# datalogger_v01_1284.net
KiCad netlist of a schematic drawn in EAGLE
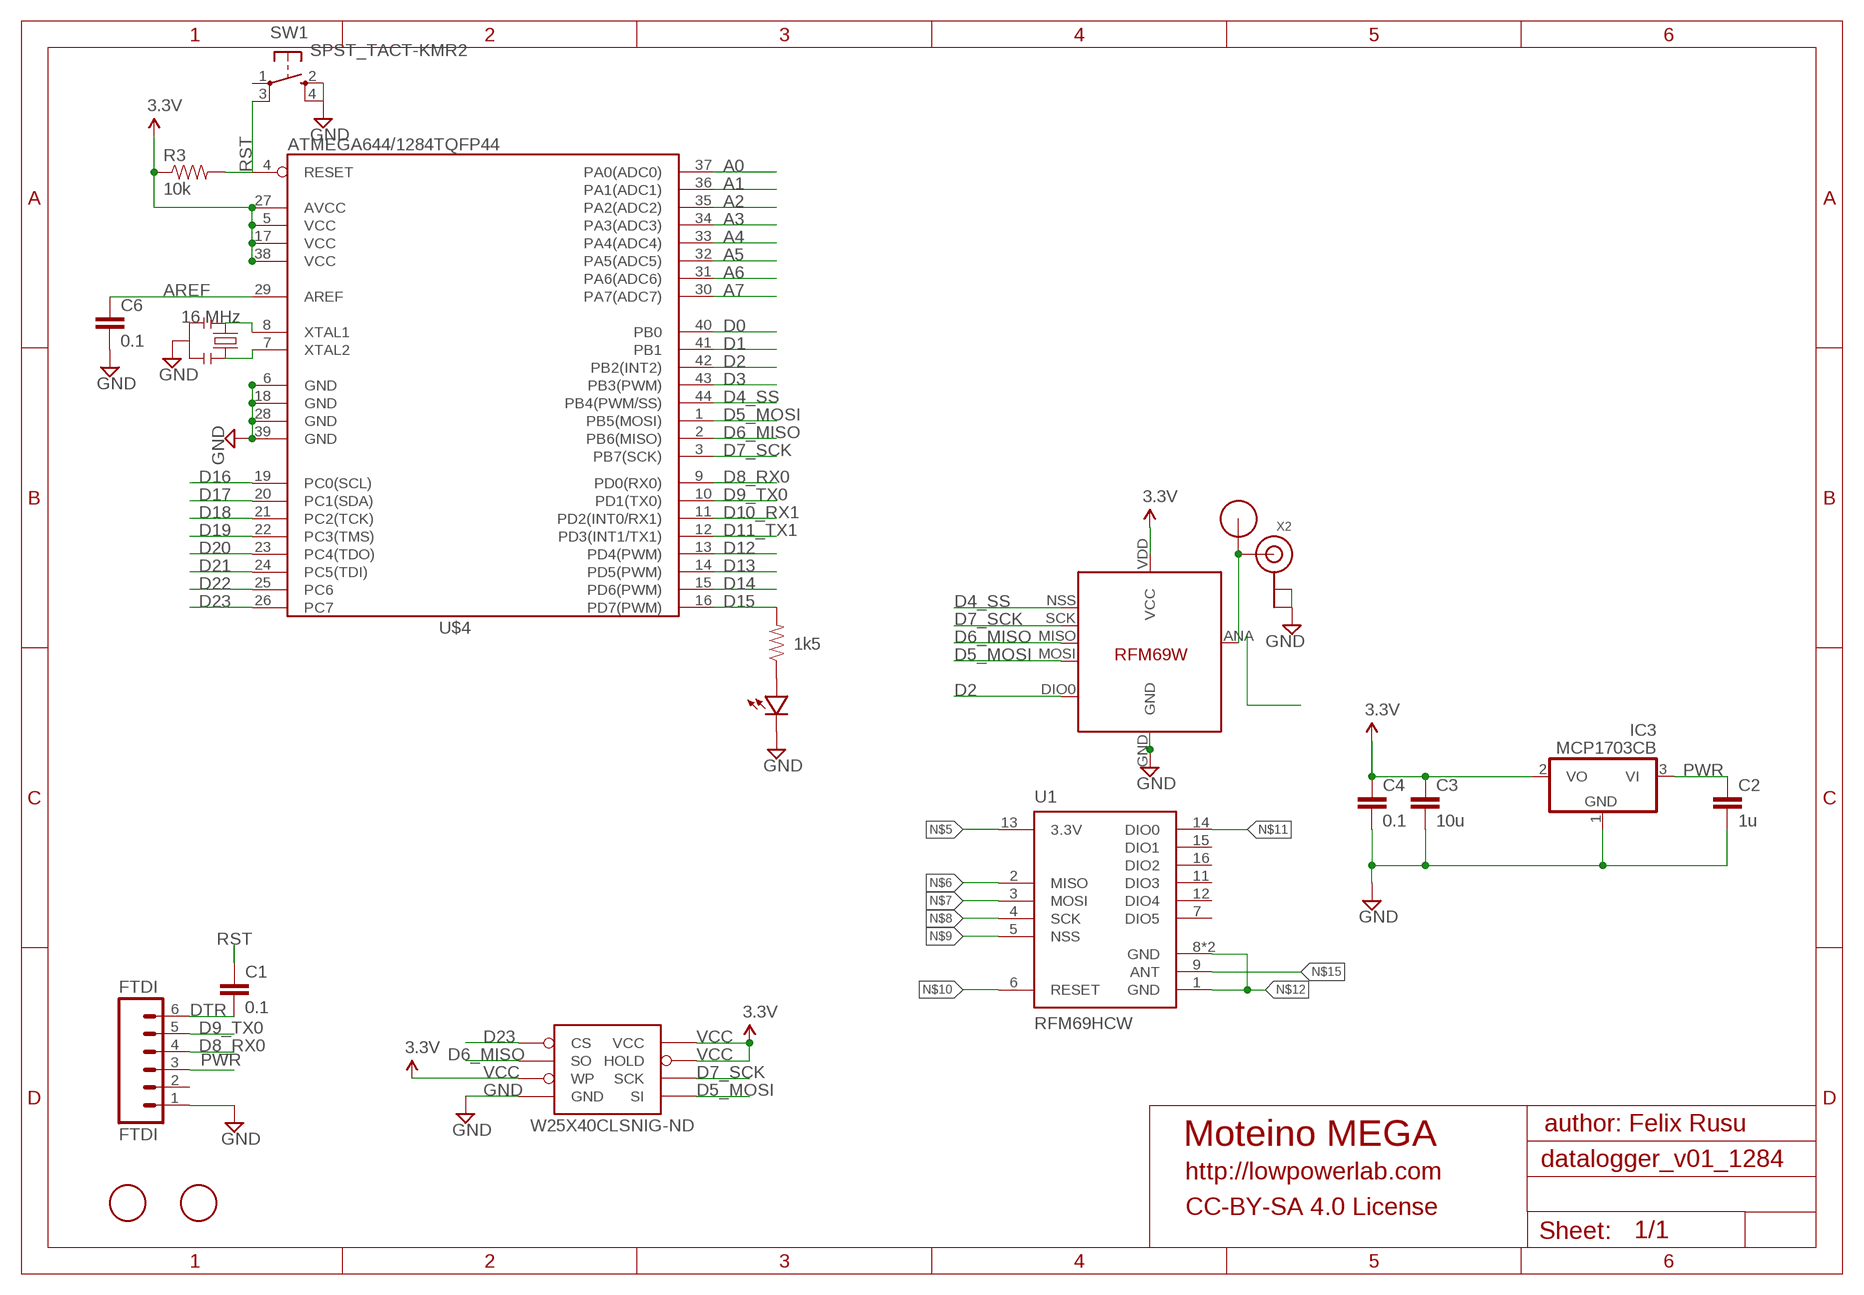
[diagram p0: schematic, sheet 1]

(export (version "E")
  (design (tool "Eeschema 10.0.6"))
  (components
    (comp (ref "C1")
      (value "0.1")
      (footprint "eagle-import:0603-CAP")
      (libsource (lib "eagle-import") (part "CAP0603-CAP"))
    )
    (comp (ref "C2")
      (value "1u")
      (footprint "eagle-import:0603-CAP")
      (libsource (lib "eagle-import") (part "CAP0603-CAP"))
    )
    (comp (ref "C3")
      (value "10u")
      (footprint "eagle-import:0805-CAP")
      (libsource (lib "eagle-import") (part "CAP0805-CAP"))
    )
    (comp (ref "C4")
      (value "0.1")
      (footprint "eagle-import:0603-CAP")
      (libsource (lib "eagle-import") (part "CAP0603-CAP"))
    )
    (comp (ref "C6")
      (value "0.1")
      (footprint "eagle-import:0603-CAP")
      (libsource (lib "eagle-import") (part "CAP0603-CAP"))
    )
    (comp (ref "FTDI")
      (value "FTDI")
      (footprint "eagle-import:1X06")
      (libsource (lib "eagle-import") (part "M06SIP"))
    )
    (comp (ref "IC3")
      (value "MCP1703CB")
      (footprint "eagle-import:SOT23")
      (libsource (lib "eagle-import") (part "MCP1703CB"))
    )
    (comp (ref "R2")
      (value "1k5")
      (footprint "eagle-import:0603-RES")
      (libsource (lib "eagle-import") (part "RESISTOR0603-RES"))
    )
    (comp (ref "R3")
      (value "10k")
      (footprint "eagle-import:0603-RES")
      (libsource (lib "eagle-import") (part "RESISTOR0603-RES"))
    )
    (comp (ref "SW1")
      (value "SPST_TACT-KMR2")
      (footprint "eagle-import:KMR2")
      (libsource (lib "eagle-import") (part "SPST_TACT-KMR2"))
    )
    (comp (ref "U$1")
      (value "RFM12B_ANTENNA")
      (footprint "eagle-import:RFM12B-ANTENNA")
      (libsource (lib "eagle-import") (part "RFM12B_ANTENNA"))
    )
    (comp (ref "U$2")
      (value "FIDUCIAL")
      (footprint "eagle-import:FIDUCIAL_1MM")
      (libsource (lib "eagle-import") (part "FIDUCIAL"))
    )
    (comp (ref "U$4")
      (value "ATMEGA644/1284TQFP44")
      (footprint "eagle-import:TQFP44")
      (libsource (lib "eagle-import") (part "ATMEGA644/1284TQFP44"))
    )
    (comp (ref "U$5")
      (value "RFM69")
      (footprint "eagle-import:RFM69W-MINPADS")
      (libsource (lib "eagle-import") (part "RFM69"))
    )
    (comp (ref "U$6")
      (value "LED0603")
      (footprint "eagle-import:0603-LED")
      (libsource (lib "eagle-import") (part "LED0603"))
    )
    (comp (ref "U$7")
      (value "FIDUCIAL")
      (footprint "eagle-import:FIDUCIAL_1MM")
      (libsource (lib "eagle-import") (part "FIDUCIAL"))
    )
    (comp (ref "U1")
      (value "RFM69HCW")
      (footprint "eagle-import:RFM69HCW-XXXS2")
      (libsource (lib "eagle-import") (part "RFM69HCW"))
    )
    (comp (ref "W25X40CLSNIG-ND")
      (value "AT25F512BWIDE_5.3MM")
      (footprint "eagle-import:SO08WIDE")
      (libsource (lib "eagle-import") (part "AT25F512BWIDE_5.3MM"))
    )
    (comp (ref "X1")
      (value "16 MHz")
      (footprint "eagle-import:RESONATOR-SMD")
      (libsource (lib "eagle-import") (part "RESONATORSMD"))
    )
    (comp (ref "X2")
      (value "ANTENNA_U.FL")
      (footprint "eagle-import:U.FL")
      (libsource (lib "eagle-import") (part "ANTENNA_U.FL"))
    )
  )
  (nets
    (net (code "1") (name "/A0") (class "Default")
      (node (ref "U$4") (pin "37") (pinfunction "PA0(ADC0)_37") (pintype "bidirectional"))
    )
    (net (code "2") (name "/A1") (class "Default")
      (node (ref "U$4") (pin "36") (pinfunction "PA1(ADC1)_36") (pintype "bidirectional"))
    )
    (net (code "3") (name "/A2") (class "Default")
      (node (ref "U$4") (pin "35") (pinfunction "PA2(ADC2)_35") (pintype "bidirectional"))
    )
    (net (code "4") (name "/A3") (class "Default")
      (node (ref "U$4") (pin "34") (pinfunction "PA3(ADC3)_34") (pintype "bidirectional"))
    )
    (net (code "5") (name "/A4") (class "Default")
      (node (ref "U$4") (pin "33") (pinfunction "PA4(ADC4)_33") (pintype "bidirectional"))
    )
    (net (code "6") (name "/A5") (class "Default")
      (node (ref "U$4") (pin "32") (pinfunction "PA5(ADC5)_32") (pintype "bidirectional"))
    )
    (net (code "7") (name "/A6") (class "Default")
      (node (ref "U$4") (pin "31") (pinfunction "PA6(ADC6)_31") (pintype "bidirectional"))
    )
    (net (code "8") (name "/A7") (class "Default")
      (node (ref "U$4") (pin "30") (pinfunction "PA7(ADC7)_30") (pintype "bidirectional"))
    )
    (net (code "9") (name "/AREF") (class "Default")
      (node (ref "C6") (pin "1") (pinfunction "1_1") (pintype "passive"))
      (node (ref "U$4") (pin "29") (pinfunction "AREF_29") (pintype "bidirectional"))
    )
    (net (code "10") (name "/D0") (class "Default")
      (node (ref "U$4") (pin "40") (pinfunction "PB0_40") (pintype "bidirectional"))
    )
    (net (code "11") (name "/D1") (class "Default")
      (node (ref "U$4") (pin "41") (pinfunction "PB1_41") (pintype "bidirectional"))
    )
    (net (code "12") (name "/D2") (class "Default")
      (node (ref "U$4") (pin "42") (pinfunction "PB2(INT2)_42") (pintype "bidirectional"))
      (node (ref "U$5") (pin "DIO0") (pinfunction "DIO0_DIO0") (pintype "open_collector"))
    )
    (net (code "13") (name "/D3") (class "Default")
      (node (ref "U$4") (pin "43") (pinfunction "PB3(PWM)_43") (pintype "bidirectional"))
    )
    (net (code "14") (name "/D4_SS") (class "Default")
      (node (ref "U$4") (pin "44") (pinfunction "PB4(PWM/SS)_44") (pintype "bidirectional"))
      (node (ref "U$5") (pin "NSS") (pinfunction "SEL_NSS") (pintype "input"))
    )
    (net (code "15") (name "/D5_MOSI") (class "Default")
      (node (ref "U$4") (pin "1") (pinfunction "PB5(MOSI)_1") (pintype "bidirectional"))
      (node (ref "U$5") (pin "MOSI") (pinfunction "MOSI_MOSI") (pintype "output"))
      (node (ref "W25X40CLSNIG-ND") (pin "5") (pinfunction "SI_5") (pintype "bidirectional"))
    )
    (net (code "16") (name "/D6_MISO") (class "Default")
      (node (ref "U$4") (pin "2") (pinfunction "PB6(MISO)_2") (pintype "bidirectional"))
      (node (ref "U$5") (pin "MISO") (pinfunction "MISO_MISO") (pintype "input"))
      (node (ref "W25X40CLSNIG-ND") (pin "2") (pinfunction "SO_2") (pintype "bidirectional"))
    )
    (net (code "17") (name "/D7_SCK") (class "Default")
      (node (ref "U$4") (pin "3") (pinfunction "PB7(SCK)_3") (pintype "bidirectional"))
      (node (ref "U$5") (pin "SCK") (pinfunction "SCK_SCK") (pintype "input"))
      (node (ref "W25X40CLSNIG-ND") (pin "6") (pinfunction "SCK_6") (pintype "bidirectional"))
    )
    (net (code "18") (name "/D8_RX0") (class "Default")
      (node (ref "FTDI") (pin "4") (pinfunction "4_4") (pintype "passive"))
      (node (ref "U$4") (pin "9") (pinfunction "PD0(RX0)_9") (pintype "bidirectional"))
    )
    (net (code "19") (name "/D9_TX0") (class "Default")
      (node (ref "FTDI") (pin "5") (pinfunction "5_5") (pintype "passive"))
      (node (ref "U$4") (pin "10") (pinfunction "PD1(TX0)_10") (pintype "bidirectional"))
    )
    (net (code "20") (name "/D10_RX1") (class "Default")
      (node (ref "U$4") (pin "11") (pinfunction "PD2(INT0/RX1)_11") (pintype "bidirectional"))
    )
    (net (code "21") (name "/D11_TX1") (class "Default")
      (node (ref "U$4") (pin "12") (pinfunction "PD3(INT1/TX1)_12") (pintype "bidirectional"))
    )
    (net (code "22") (name "/D12") (class "Default")
      (node (ref "U$4") (pin "13") (pinfunction "PD4(PWM)_13") (pintype "bidirectional"))
    )
    (net (code "23") (name "/D13") (class "Default")
      (node (ref "U$4") (pin "14") (pinfunction "PD5(PWM)_14") (pintype "bidirectional"))
    )
    (net (code "24") (name "/D14") (class "Default")
      (node (ref "U$4") (pin "15") (pinfunction "PD6(PWM)_15") (pintype "bidirectional"))
    )
    (net (code "25") (name "/D15") (class "Default")
      (node (ref "R2") (pin "2") (pinfunction "2_2") (pintype "passive"))
      (node (ref "U$4") (pin "16") (pinfunction "PD7(PWM)_16") (pintype "bidirectional"))
    )
    (net (code "26") (name "/D16") (class "Default")
      (node (ref "U$4") (pin "19") (pinfunction "PC0(SCL)_19") (pintype "bidirectional"))
    )
    (net (code "27") (name "/D17") (class "Default")
      (node (ref "U$4") (pin "20") (pinfunction "PC1(SDA)_20") (pintype "bidirectional"))
    )
    (net (code "28") (name "/D18") (class "Default")
      (node (ref "U$4") (pin "21") (pinfunction "PC2(TCK)_21") (pintype "bidirectional"))
    )
    (net (code "29") (name "/D19") (class "Default")
      (node (ref "U$4") (pin "22") (pinfunction "PC3(TMS)_22") (pintype "bidirectional"))
    )
    (net (code "30") (name "/D20") (class "Default")
      (node (ref "U$4") (pin "23") (pinfunction "PC4(TDO)_23") (pintype "bidirectional"))
    )
    (net (code "31") (name "/D21") (class "Default")
      (node (ref "U$4") (pin "24") (pinfunction "PC5(TDI)_24") (pintype "bidirectional"))
    )
    (net (code "32") (name "/D22") (class "Default")
      (node (ref "U$4") (pin "25") (pinfunction "PC6_25") (pintype "bidirectional"))
    )
    (net (code "33") (name "/D23") (class "Default")
      (node (ref "U$4") (pin "26") (pinfunction "PC7_26") (pintype "bidirectional"))
      (node (ref "W25X40CLSNIG-ND") (pin "1") (pinfunction "CS_1") (pintype "bidirectional"))
    )
    (net (code "34") (name "/DTR") (class "Default")
      (node (ref "C1") (pin "2") (pinfunction "2_2") (pintype "passive"))
      (node (ref "FTDI") (pin "6") (pinfunction "6_6") (pintype "passive"))
    )
    (net (code "35") (name "/PWR") (class "Default")
      (node (ref "C2") (pin "1") (pinfunction "1_1") (pintype "passive"))
      (node (ref "FTDI") (pin "3") (pinfunction "3_3") (pintype "passive"))
      (node (ref "IC3") (pin "3") (pinfunction "VI_3") (pintype "input"))
    )
    (net (code "36") (name "/RST") (class "Default")
      (node (ref "C1") (pin "1") (pinfunction "1_1") (pintype "passive"))
      (node (ref "R3") (pin "2") (pinfunction "2_2") (pintype "passive"))
      (node (ref "SW1") (pin "3") (pinfunction "P1_3") (pintype "passive"))
      (node (ref "U$4") (pin "4") (pinfunction "RESET_4") (pintype "bidirectional"))
    )
    (net (code "37") (name "3.3V") (class "Default")
      (node (ref "C3") (pin "1") (pinfunction "1_1") (pintype "passive"))
      (node (ref "C4") (pin "1") (pinfunction "1_1") (pintype "passive"))
      (node (ref "IC3") (pin "2") (pinfunction "VO_2") (pintype "passive"))
      (node (ref "R3") (pin "1") (pinfunction "1_1") (pintype "passive"))
      (node (ref "U$4") (pin "17") (pinfunction "VCC_17") (pintype "bidirectional"))
      (node (ref "U$4") (pin "27") (pinfunction "AVCC_27") (pintype "bidirectional"))
      (node (ref "U$4") (pin "38") (pinfunction "VCC_38") (pintype "bidirectional"))
      (node (ref "U$4") (pin "5") (pinfunction "VCC_5") (pintype "bidirectional"))
      (node (ref "U$5") (pin "VDD") (pinfunction "VCC_VDD") (pintype "power_in"))
      (node (ref "W25X40CLSNIG-ND") (pin "3") (pinfunction "WP_3") (pintype "bidirectional"))
      (node (ref "W25X40CLSNIG-ND") (pin "7") (pinfunction "HOLD_7") (pintype "bidirectional"))
      (node (ref "W25X40CLSNIG-ND") (pin "8") (pinfunction "VCC_8") (pintype "bidirectional"))
    )
    (net (code "38") (name "GND") (class "Default")
      (node (ref "C2") (pin "2") (pinfunction "2_2") (pintype "passive"))
      (node (ref "C3") (pin "2") (pinfunction "2_2") (pintype "passive"))
      (node (ref "C4") (pin "2") (pinfunction "2_2") (pintype "passive"))
      (node (ref "C6") (pin "2") (pinfunction "2_2") (pintype "passive"))
      (node (ref "FTDI") (pin "1") (pinfunction "1_1") (pintype "passive"))
      (node (ref "IC3") (pin "1") (pinfunction "GND_1") (pintype "passive"))
      (node (ref "SW1") (pin "2") (pinfunction "S_2") (pintype "passive"))
      (node (ref "SW1") (pin "4") (pinfunction "S1_4") (pintype "passive"))
      (node (ref "U$4") (pin "18") (pinfunction "GND_18") (pintype "bidirectional"))
      (node (ref "U$4") (pin "28") (pinfunction "GND_28") (pintype "bidirectional"))
      (node (ref "U$4") (pin "39") (pinfunction "GND_39") (pintype "bidirectional"))
      (node (ref "U$4") (pin "6") (pinfunction "GND_6") (pintype "bidirectional"))
      (node (ref "U$5") (pin "GND") (pinfunction "GND_GND") (pintype "power_in"))
      (node (ref "U$6") (pin "MINUS") (pinfunction "MINUS_MINUS") (pintype "passive"))
      (node (ref "W25X40CLSNIG-ND") (pin "4") (pinfunction "GND_4") (pintype "bidirectional"))
      (node (ref "X1") (pin "2") (pinfunction "2_2") (pintype "passive"))
      (node (ref "X2") (pin "1") (pinfunction "GND_1") (pintype "passive"))
      (node (ref "X2") (pin "2") (pinfunction "GND_2") (pintype "passive"))
    )
    (net (code "39") (name "N$5") (class "Default")
      (node (ref "U1") (pin "13") (pinfunction "3.3V_13") (pintype "power_in"))
    )
    (net (code "40") (name "N$6") (class "Default")
      (node (ref "U1") (pin "2") (pinfunction "MISO_2") (pintype "bidirectional"))
    )
    (net (code "41") (name "N$7") (class "Default")
      (node (ref "U1") (pin "3") (pinfunction "MOSI_3") (pintype "input"))
    )
    (net (code "42") (name "N$8") (class "Default")
      (node (ref "U1") (pin "4") (pinfunction "SCK_4") (pintype "input"))
    )
    (net (code "43") (name "N$9") (class "Default")
      (node (ref "U1") (pin "5") (pinfunction "NSS_5") (pintype "input"))
    )
    (net (code "44") (name "N$10") (class "Default")
      (node (ref "U1") (pin "6") (pinfunction "RESET_6") (pintype "input"))
    )
    (net (code "45") (name "N$11") (class "Default")
      (node (ref "U1") (pin "14") (pinfunction "DIO0_14") (pintype "bidirectional"))
    )
    (net (code "46") (name "N$12") (class "Default")
      (node (ref "U1") (pin "1") (pinfunction "GND_1") (pintype "power_in"))
      (node (ref "U1") (pin "10") (pinfunction "GND_10") (pintype "power_in"))
      (node (ref "U1") (pin "8") (pinfunction "GND_8") (pintype "power_in"))
    )
    (net (code "47") (name "N$15") (class "Default")
      (node (ref "U1") (pin "9") (pinfunction "ANT_9") (pintype "passive"))
    )
    (net (code "48") (name "Net-(R2-Pad1)") (class "Default")
      (node (ref "R2") (pin "1") (pinfunction "1_1") (pintype "passive"))
      (node (ref "U$6") (pin "PLUS") (pinfunction "PLUS_PLUS") (pintype "passive"))
    )
    (net (code "49") (name "Net-(U$1-1)") (class "Default")
      (node (ref "U$1") (pin "P$1") (pinfunction "1_P$1") (pintype "bidirectional"))
      (node (ref "U$5") (pin "ANA") (pinfunction "ANT_ANA") (pintype "passive"))
      (node (ref "X2") (pin "3") (pinfunction "SIGNAL_3") (pintype "passive"))
    )
    (net (code "50") (name "Net-(U$4-XTAL1)") (class "Default")
      (node (ref "U$4") (pin "8") (pinfunction "XTAL1_8") (pintype "bidirectional"))
      (node (ref "X1") (pin "1") (pinfunction "1_1") (pintype "passive"))
    )
    (net (code "51") (name "Net-(U$4-XTAL2)") (class "Default")
      (node (ref "U$4") (pin "7") (pinfunction "XTAL2_7") (pintype "bidirectional"))
      (node (ref "X1") (pin "3") (pinfunction "3_3") (pintype "passive"))
    )
    (net (code "52") (name "unconnected-(FTDI-Pad2)") (class "Default")
      (node (ref "FTDI") (pin "2") (pinfunction "2_2") (pintype "passive"))
    )
    (net (code "53") (name "unconnected-(SW1-P-Pad1)") (class "Default")
      (node (ref "SW1") (pin "1") (pinfunction "P_1") (pintype "passive"))
    )
    (net (code "54") (name "unconnected-(U1-DIO1-Pad15)") (class "Default")
      (node (ref "U1") (pin "15") (pinfunction "DIO1_15") (pintype "bidirectional"))
    )
    (net (code "55") (name "unconnected-(U1-DIO2-Pad16)") (class "Default")
      (node (ref "U1") (pin "16") (pinfunction "DIO2_16") (pintype "bidirectional"))
    )
    (net (code "56") (name "unconnected-(U1-DIO3-Pad11)") (class "Default")
      (node (ref "U1") (pin "11") (pinfunction "DIO3_11") (pintype "bidirectional"))
    )
    (net (code "57") (name "unconnected-(U1-DIO4-Pad12)") (class "Default")
      (node (ref "U1") (pin "12") (pinfunction "DIO4_12") (pintype "bidirectional"))
    )
    (net (code "58") (name "unconnected-(U1-DIO5-Pad7)") (class "Default")
      (node (ref "U1") (pin "7") (pinfunction "DIO5_7") (pintype "bidirectional"))
    )
  )
)
